# Logic.net
KiCad netlist of a schematic drawn in Altium Designer
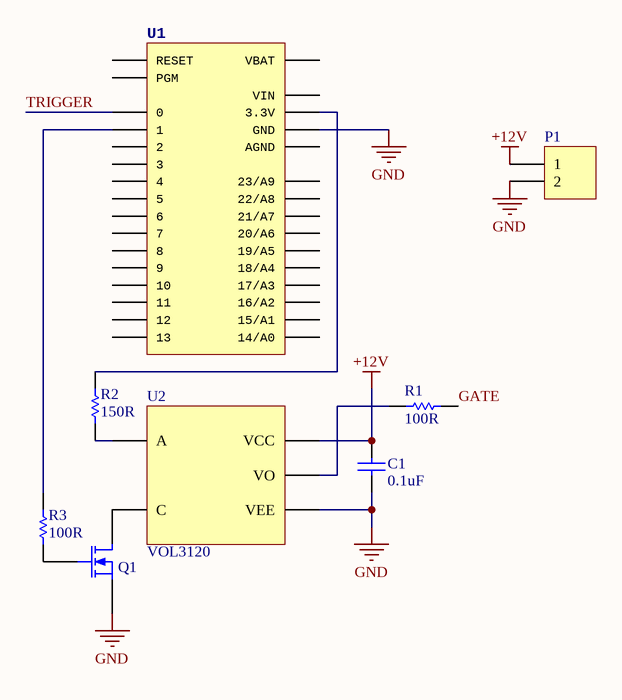
[diagram p0: Logic.SchDoc]

(export (version "E")
  (design (tool "Eeschema 10.0.6"))
  (components
    (comp (ref "C1")
      (value "0.1uF")
      (footprint "CAPC0603(1608)100_L")
      (description "CAP 100nF 100V Â±10% 0603 (1608 Metric) Thickness 1mm SMD")
      (fields (field (name "TOLERANCE") "Â±10%"))
      (libsource (lib "Altium Inc") (part "CAP"))
    )
    (comp (ref "P1")
      (value "~")
      (footprint "HDR1X2")
      (description "Header, 2-Pin")
      (fields (field (name "PUBLISHER") "Altium Limited"))
      (libsource (lib "Miscellaneous Connectors") (part "Header 2"))
    )
    (comp (ref "Q1")
      (value "MOSFET-N")
      (footprint "SOT23-3")
      (description "N-Channel MOSFET")
      (fields (field (name "PUBLISHER") "Altium Limited"))
      (libsource (lib "Components") (part "MOSFET-N"))
    )
    (comp (ref "R1")
      (value "100R")
      (footprint "RESC0603(1608)_M")
      (description "100R 0.1W 5% 0603 (1608 Metric)  SMD")
      (fields (field (name "TOLERANCE") "5 %") (field (name "POWER") "0.1 W"))
      (libsource (lib "Altium Inc") (part "RES"))
    )
    (comp (ref "R2")
      (value "150R")
      (footprint "RESC0603(1608)_M")
      (description "150R 0.1W 5% 0603 (1608 Metric)  SMD")
      (fields (field (name "POWER") "0.1 W") (field (name "TOLERANCE") "5 %"))
      (libsource (lib "Altium Inc") (part "RES"))
    )
    (comp (ref "R3")
      (value "100R")
      (footprint "RESC0603(1608)_M")
      (description "100R 0.1W 5% 0603 (1608 Metric)  SMD")
      (fields (field (name "TOLERANCE") "5 %") (field (name "POWER") "0.1 W"))
      (libsource (lib "Altium Inc") (part "RES"))
    )
    (comp (ref "U1")
      (value "~")
      (footprint "TEENSY_3.0_BASIC")
      (libsource (lib "Components") (part "TEENSY_3.0_BASIC"))
    )
    (comp (ref "U2") (value "VOL3120") (footprint "LSOP-5") (libsource (lib "Components") (part "VOL3120")))
  )
  (nets
    (net (code "1") (name "+12V") (class "Default")
      (node (ref "C1") (pin "2") (pinfunction "2_2") (pintype "passive"))
      (node (ref "P1") (pin "1") (pinfunction "1_1") (pintype "passive"))
      (node (ref "U2") (pin "5") (pinfunction "VCC_5") (pintype "passive"))
    )
    (net (code "2") (name "/GATE") (class "Default")
      (node (ref "R1") (pin "1") (pinfunction "1_1") (pintype "passive"))
    )
    (net (code "3") (name "/TRIGGER") (class "Default")
      (node (ref "U1") (pin "0") (pinfunction "0_0") (pintype "passive"))
    )
    (net (code "4") (name "GND") (class "Default")
      (node (ref "C1") (pin "1") (pinfunction "1_1") (pintype "passive"))
      (node (ref "P1") (pin "2") (pinfunction "2_2") (pintype "passive"))
      (node (ref "Q1") (pin "3") (pinfunction "S_3") (pintype "passive"))
      (node (ref "U1") (pin "GND_GND1") (pinfunction "GND_GND_GND1") (pintype "power_in"))
      (node (ref "U2") (pin "3") (pinfunction "VEE_3") (pintype "passive"))
    )
    (net (code "5") (name "Net-(Q1-D)") (class "Default")
      (node (ref "Q1") (pin "2") (pinfunction "D_2") (pintype "passive"))
      (node (ref "U2") (pin "2") (pinfunction "C_2") (pintype "passive"))
    )
    (net (code "6") (name "Net-(Q1-G)") (class "Default")
      (node (ref "Q1") (pin "1") (pinfunction "G_1") (pintype "passive"))
      (node (ref "R3") (pin "1") (pinfunction "1_1") (pintype "passive"))
    )
    (net (code "7") (name "Net-(R3-Pad2)") (class "Default")
      (node (ref "R3") (pin "2") (pinfunction "2_2") (pintype "passive"))
      (node (ref "U1") (pin "1") (pinfunction "1_1") (pintype "passive"))
    )
    (net (code "8") (name "Net-(U1-3.3V)") (class "Default")
      (node (ref "R2") (pin "2") (pinfunction "2_2") (pintype "passive"))
      (node (ref "U1") (pin "3.3V_3.3V1") (pinfunction "3.3V_3.3V_3.3V1") (pintype "power_in"))
    )
    (net (code "9") (name "Net-(U2-A)") (class "Default")
      (node (ref "R2") (pin "1") (pinfunction "1_1") (pintype "passive"))
      (node (ref "U2") (pin "1") (pinfunction "A_1") (pintype "passive"))
    )
    (net (code "10") (name "Net-(U2-VO)") (class "Default")
      (node (ref "R1") (pin "2") (pinfunction "2_2") (pintype "passive"))
      (node (ref "U2") (pin "4") (pinfunction "VO_4") (pintype "passive"))
    )
    (net (code "11") (name "unconnected-(U1-Pad2)") (class "Default")
      (node (ref "U1") (pin "2") (pinfunction "2_2") (pintype "passive"))
    )
    (net (code "12") (name "unconnected-(U1-Pad3)") (class "Default")
      (node (ref "U1") (pin "3") (pinfunction "3_3") (pintype "passive"))
    )
    (net (code "13") (name "unconnected-(U1-Pad4)") (class "Default")
      (node (ref "U1") (pin "4") (pinfunction "4_4") (pintype "passive"))
    )
    (net (code "14") (name "unconnected-(U1-Pad5)") (class "Default")
      (node (ref "U1") (pin "5") (pinfunction "5_5") (pintype "passive"))
    )
    (net (code "15") (name "unconnected-(U1-Pad6)") (class "Default")
      (node (ref "U1") (pin "6") (pinfunction "6_6") (pintype "passive"))
    )
    (net (code "16") (name "unconnected-(U1-Pad7)") (class "Default")
      (node (ref "U1") (pin "7") (pinfunction "7_7") (pintype "passive"))
    )
    (net (code "17") (name "unconnected-(U1-Pad8)") (class "Default")
      (node (ref "U1") (pin "8") (pinfunction "8_8") (pintype "passive"))
    )
    (net (code "18") (name "unconnected-(U1-Pad9)") (class "Default")
      (node (ref "U1") (pin "9") (pinfunction "9_9") (pintype "passive"))
    )
    (net (code "19") (name "unconnected-(U1-Pad10)") (class "Default")
      (node (ref "U1") (pin "10") (pinfunction "10_10") (pintype "passive"))
    )
    (net (code "20") (name "unconnected-(U1-Pad11)") (class "Default")
      (node (ref "U1") (pin "11") (pinfunction "11_11") (pintype "passive"))
    )
    (net (code "21") (name "unconnected-(U1-Pad12)") (class "Default")
      (node (ref "U1") (pin "12") (pinfunction "12_12") (pintype "passive"))
    )
    (net (code "22") (name "unconnected-(U1-Pad13)") (class "Default")
      (node (ref "U1") (pin "13") (pinfunction "13_13") (pintype "passive"))
    )
    (net (code "23") (name "unconnected-(U1-Pad14{slash}A0)") (class "Default")
      (node (ref "U1") (pin "14/A0") (pinfunction "14/A0_14/A0") (pintype "passive"))
    )
    (net (code "24") (name "unconnected-(U1-Pad15{slash}A1)") (class "Default")
      (node (ref "U1") (pin "15/A1") (pinfunction "15/A1_15/A1") (pintype "passive"))
    )
    (net (code "25") (name "unconnected-(U1-Pad16{slash}A2)") (class "Default")
      (node (ref "U1") (pin "16/A2") (pinfunction "16/A2_16/A2") (pintype "passive"))
    )
    (net (code "26") (name "unconnected-(U1-Pad17{slash}A3)") (class "Default")
      (node (ref "U1") (pin "17/A3") (pinfunction "17/A3_17/A3") (pintype "passive"))
    )
    (net (code "27") (name "unconnected-(U1-Pad18{slash}A4)") (class "Default")
      (node (ref "U1") (pin "18/A4") (pinfunction "18/A4_18/A4") (pintype "passive"))
    )
    (net (code "28") (name "unconnected-(U1-Pad19{slash}A5)") (class "Default")
      (node (ref "U1") (pin "19/A5") (pinfunction "19/A5_19/A5") (pintype "passive"))
    )
    (net (code "29") (name "unconnected-(U1-Pad20{slash}A6)") (class "Default")
      (node (ref "U1") (pin "20/A6") (pinfunction "20/A6_20/A6") (pintype "passive"))
    )
    (net (code "30") (name "unconnected-(U1-Pad21{slash}A7)") (class "Default")
      (node (ref "U1") (pin "21/A7") (pinfunction "21/A7_21/A7") (pintype "passive"))
    )
    (net (code "31") (name "unconnected-(U1-Pad22{slash}A8)") (class "Default")
      (node (ref "U1") (pin "22/A8") (pinfunction "22/A8_22/A8") (pintype "passive"))
    )
    (net (code "32") (name "unconnected-(U1-Pad23{slash}A9)") (class "Default")
      (node (ref "U1") (pin "23/A9") (pinfunction "23/A9_23/A9") (pintype "passive"))
    )
    (net (code "33") (name "unconnected-(U1-PadAGND)") (class "Default")
      (node (ref "U1") (pin "AGND") (pinfunction "AGND_AGND") (pintype "power_in"))
    )
    (net (code "34") (name "unconnected-(U1-PadPGM)") (class "Default")
      (node (ref "U1") (pin "PGM") (pinfunction "PGM_PGM") (pintype "passive"))
    )
    (net (code "35") (name "unconnected-(U1-PadRESET)") (class "Default")
      (node (ref "U1") (pin "RESET") (pinfunction "RESET_RESET") (pintype "passive"))
    )
    (net (code "36") (name "unconnected-(U1-PadVBAT)") (class "Default")
      (node (ref "U1") (pin "VBAT") (pinfunction "VBAT_VBAT") (pintype "power_in"))
    )
    (net (code "37") (name "unconnected-(U1-PadVIN)") (class "Default")
      (node (ref "U1") (pin "VIN") (pinfunction "VIN_VIN") (pintype "power_in"))
    )
  )
)
